# MCU.net
KiCad netlist of a schematic drawn in Altium Designer
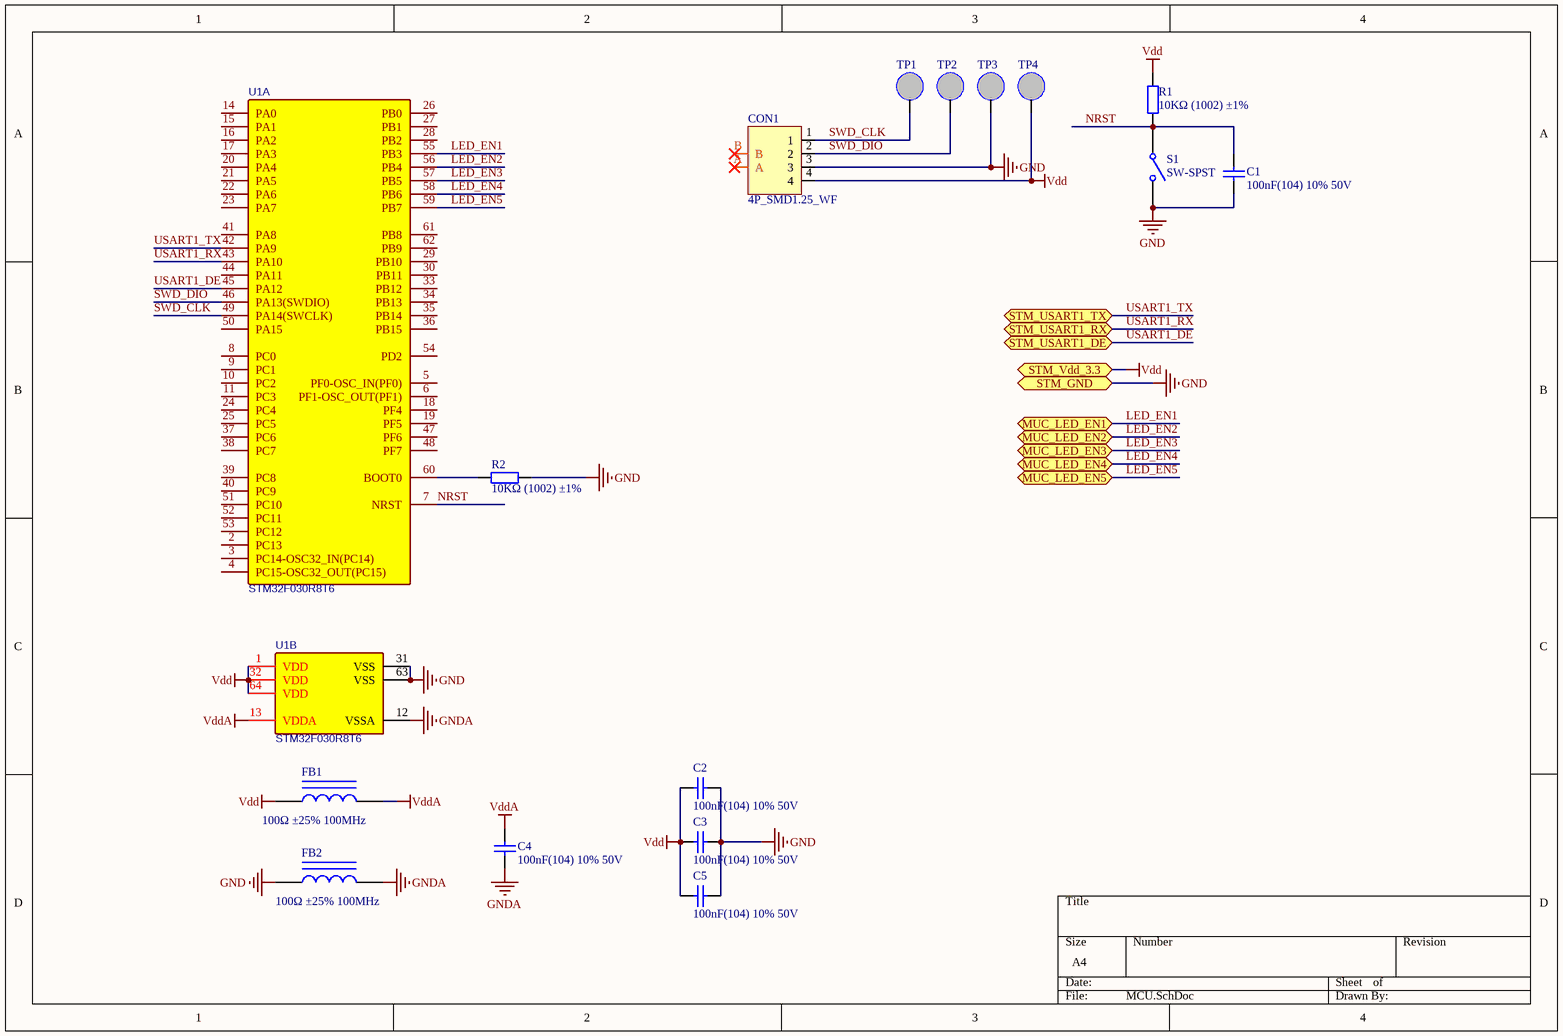
[diagram p0: MCU.SchDoc]

(export (version "E")
  (design (tool "Eeschema 10.0.6"))
  (components
    (comp (ref "C1")
      (value "100nF(104) 10% 50V")
      (footprint "0805_C")
      (description "贴片电容")
      (libsource (lib "Miscellaneous Devices LC") (part "0805 100nF(104) 10% 50V"))
    )
    (comp (ref "C2")
      (value "100nF(104) 10% 50V")
      (footprint "0805_C")
      (description "贴片电容")
      (libsource (lib "Miscellaneous Devices LC") (part "0805 100nF(104) 10% 50V"))
    )
    (comp (ref "C3")
      (value "100nF(104) 10% 50V")
      (footprint "0805_C")
      (description "贴片电容")
      (libsource (lib "Miscellaneous Devices LC") (part "0805 100nF(104) 10% 50V"))
    )
    (comp (ref "C4")
      (value "100nF(104) 10% 50V")
      (footprint "0805_C")
      (description "贴片电容")
      (libsource (lib "Miscellaneous Devices LC") (part "0805 100nF(104) 10% 50V"))
    )
    (comp (ref "C5")
      (value "100nF(104) 10% 50V")
      (footprint "0805_C")
      (description "贴片电容")
      (libsource (lib "Miscellaneous Devices LC") (part "0805 100nF(104) 10% 50V"))
    )
    (comp (ref "CON1")
      (value "4P_SMD1.25_WF")
      (footprint "MX 1.25-LS-4P")
      (libsource (lib "mylib") (part "4P_XH2.54_W"))
    )
    (comp (ref "FB1")
      (value "100Ω ±25% 100MHz")
      (footprint "0805_L")
      (description "贴片磁珠")
      (libsource (lib "Miscellaneous Devices LC") (part "0805 100Ω 25% 100MHz"))
    )
    (comp (ref "FB2")
      (value "100Ω ±25% 100MHz")
      (footprint "0805_L")
      (description "贴片磁珠")
      (libsource (lib "Miscellaneous Devices LC") (part "0805 100Ω 25% 100MHz"))
    )
    (comp (ref "R1")
      (value "10KΩ (1002) ±1%")
      (footprint "0805_R")
      (description "贴片电阻")
      (libsource (lib "Miscellaneous Devices LC") (part "0805 10KΩ (1002) 1%"))
    )
    (comp (ref "R2")
      (value "10KΩ (1002) ±1%")
      (footprint "0805_R")
      (description "贴片电阻")
      (libsource (lib "") (part "0805 10KΩ (1002) 1%_1"))
    )
    (comp (ref "S1")
      (value "SW-SPST")
      (footprint "key")
      (description "Single-Pole, Single-Throw Switch")
      (fields (field (name "PUBLISHER") "Altium Limited"))
      (libsource (lib "Miscellaneous Devices") (part "SW-SPST"))
    )
    (comp (ref "TP1") (value "TP") (footprint "TP") (libsource (lib "mylib") (part "TP")))
    (comp (ref "TP2") (value "TP") (footprint "TP") (libsource (lib "mylib") (part "TP")))
    (comp (ref "TP3") (value "TP") (footprint "TP") (libsource (lib "mylib") (part "TP")))
    (comp (ref "TP4") (value "TP") (footprint "TP") (libsource (lib "mylib") (part "TP")))
    (comp (ref "U1")
      (value "STM32F030R8T6")
      (footprint "LQFP-64_10X10X05P")
      (fields (field (name "BOM_SUPPLIER PART") "C39105") (field (name "SUBPART_NO") "1"))
      (libsource (lib "mylib") (part "STM32F030R8T6"))
    )
  )
  (nets
    (net (code "1") (name "/LED_EN1") (class "Default")
      (node (ref "U1") (pin "55") (pinfunction "PB3_55") (pintype "passive"))
    )
    (net (code "2") (name "/LED_EN2") (class "Default")
      (node (ref "U1") (pin "56") (pinfunction "PB4_56") (pintype "passive"))
    )
    (net (code "3") (name "/LED_EN3") (class "Default")
      (node (ref "U1") (pin "57") (pinfunction "PB5_57") (pintype "passive"))
    )
    (net (code "4") (name "/LED_EN4") (class "Default")
      (node (ref "U1") (pin "58") (pinfunction "PB6_58") (pintype "passive"))
    )
    (net (code "5") (name "/LED_EN5") (class "Default")
      (node (ref "U1") (pin "59") (pinfunction "PB7_59") (pintype "passive"))
    )
    (net (code "6") (name "/NRST") (class "Default")
      (node (ref "C1") (pin "2") (pinfunction "2_2") (pintype "passive"))
      (node (ref "R1") (pin "1") (pinfunction "1_1") (pintype "passive"))
      (node (ref "S1") (pin "1") (pinfunction "COMMON_1") (pintype "passive"))
      (node (ref "U1") (pin "7") (pinfunction "NRST_7") (pintype "passive"))
    )
    (net (code "7") (name "/SWD_CLK") (class "Default")
      (node (ref "CON1") (pin "1") (pinfunction "1_1") (pintype "passive"))
      (node (ref "TP1") (pin "1") (pinfunction "1_1") (pintype "passive"))
      (node (ref "U1") (pin "49") (pinfunction "PA14(SWCLK)_49") (pintype "passive"))
    )
    (net (code "8") (name "/SWD_DIO") (class "Default")
      (node (ref "CON1") (pin "2") (pinfunction "2_2") (pintype "passive"))
      (node (ref "TP2") (pin "1") (pinfunction "1_1") (pintype "passive"))
      (node (ref "U1") (pin "46") (pinfunction "PA13(SWDIO)_46") (pintype "passive"))
    )
    (net (code "9") (name "/USART1_DE") (class "Default")
      (node (ref "U1") (pin "45") (pinfunction "PA12_45") (pintype "passive"))
    )
    (net (code "10") (name "/USART1_RX") (class "Default")
      (node (ref "U1") (pin "43") (pinfunction "PA10_43") (pintype "passive"))
    )
    (net (code "11") (name "/USART1_TX") (class "Default")
      (node (ref "U1") (pin "42") (pinfunction "PA9_42") (pintype "passive"))
    )
    (net (code "12") (name "GND") (class "Default")
      (node (ref "C1") (pin "1") (pinfunction "1_1") (pintype "passive"))
      (node (ref "C2") (pin "1") (pinfunction "1_1") (pintype "passive"))
      (node (ref "C3") (pin "1") (pinfunction "1_1") (pintype "passive"))
      (node (ref "C5") (pin "1") (pinfunction "1_1") (pintype "passive"))
      (node (ref "CON1") (pin "3") (pinfunction "3_3") (pintype "passive"))
      (node (ref "FB2") (pin "1") (pinfunction "1_1") (pintype "passive"))
      (node (ref "R2") (pin "2") (pinfunction "2_2") (pintype "passive"))
      (node (ref "S1") (pin "2") (pinfunction "NO_2") (pintype "passive"))
      (node (ref "TP3") (pin "1") (pinfunction "1_1") (pintype "passive"))
      (node (ref "U1") (pin "31") (pinfunction "VSS_31") (pintype "passive"))
      (node (ref "U1") (pin "63") (pinfunction "VSS_63") (pintype "passive"))
    )
    (net (code "13") (name "GNDA") (class "Default")
      (node (ref "C4") (pin "1") (pinfunction "1_1") (pintype "passive"))
      (node (ref "FB2") (pin "2") (pinfunction "2_2") (pintype "passive"))
      (node (ref "U1") (pin "12") (pinfunction "VSSA_12") (pintype "passive"))
    )
    (net (code "14") (name "Net-(U1A-BOOT0)") (class "Default")
      (node (ref "R2") (pin "1") (pinfunction "1_1") (pintype "passive"))
      (node (ref "U1") (pin "60") (pinfunction "BOOT0_60") (pintype "passive"))
    )
    (net (code "15") (name "Vdd") (class "Default")
      (node (ref "C2") (pin "2") (pinfunction "2_2") (pintype "passive"))
      (node (ref "C3") (pin "2") (pinfunction "2_2") (pintype "passive"))
      (node (ref "C5") (pin "2") (pinfunction "2_2") (pintype "passive"))
      (node (ref "CON1") (pin "4") (pinfunction "4_4") (pintype "passive"))
      (node (ref "FB1") (pin "1") (pinfunction "1_1") (pintype "passive"))
      (node (ref "R1") (pin "2") (pinfunction "2_2") (pintype "passive"))
      (node (ref "TP4") (pin "1") (pinfunction "1_1") (pintype "passive"))
      (node (ref "U1") (pin "1") (pinfunction "VDD_1") (pintype "passive"))
      (node (ref "U1") (pin "32") (pinfunction "VDD_32") (pintype "passive"))
      (node (ref "U1") (pin "64") (pinfunction "VDD_64") (pintype "passive"))
    )
    (net (code "16") (name "VddA") (class "Default")
      (node (ref "C4") (pin "2") (pinfunction "2_2") (pintype "passive"))
      (node (ref "FB1") (pin "2") (pinfunction "2_2") (pintype "passive"))
      (node (ref "U1") (pin "13") (pinfunction "VDDA_13") (pintype "passive"))
    )
    (net (code "17") (name "unconnected-(CON1-PadA)") (class "Default")
      (node (ref "CON1") (pin "A") (pinfunction "A_A") (pintype "passive+no_connect"))
    )
    (net (code "18") (name "unconnected-(CON1-PadB)") (class "Default")
      (node (ref "CON1") (pin "B") (pinfunction "B_B") (pintype "passive+no_connect"))
    )
    (net (code "19") (name "unconnected-(U1A-PA0-Pad14)") (class "Default")
      (node (ref "U1") (pin "14") (pinfunction "PA0_14") (pintype "passive"))
    )
    (net (code "20") (name "unconnected-(U1A-PA1-Pad15)") (class "Default")
      (node (ref "U1") (pin "15") (pinfunction "PA1_15") (pintype "passive"))
    )
    (net (code "21") (name "unconnected-(U1A-PA2-Pad16)") (class "Default")
      (node (ref "U1") (pin "16") (pinfunction "PA2_16") (pintype "passive"))
    )
    (net (code "22") (name "unconnected-(U1A-PA3-Pad17)") (class "Default")
      (node (ref "U1") (pin "17") (pinfunction "PA3_17") (pintype "passive"))
    )
    (net (code "23") (name "unconnected-(U1A-PA4-Pad20)") (class "Default")
      (node (ref "U1") (pin "20") (pinfunction "PA4_20") (pintype "passive"))
    )
    (net (code "24") (name "unconnected-(U1A-PA5-Pad21)") (class "Default")
      (node (ref "U1") (pin "21") (pinfunction "PA5_21") (pintype "passive"))
    )
    (net (code "25") (name "unconnected-(U1A-PA6-Pad22)") (class "Default")
      (node (ref "U1") (pin "22") (pinfunction "PA6_22") (pintype "passive"))
    )
    (net (code "26") (name "unconnected-(U1A-PA7-Pad23)") (class "Default")
      (node (ref "U1") (pin "23") (pinfunction "PA7_23") (pintype "passive"))
    )
    (net (code "27") (name "unconnected-(U1A-PA8-Pad41)") (class "Default")
      (node (ref "U1") (pin "41") (pinfunction "PA8_41") (pintype "passive"))
    )
    (net (code "28") (name "unconnected-(U1A-PA11-Pad44)") (class "Default")
      (node (ref "U1") (pin "44") (pinfunction "PA11_44") (pintype "passive"))
    )
    (net (code "29") (name "unconnected-(U1A-PA15-Pad50)") (class "Default")
      (node (ref "U1") (pin "50") (pinfunction "PA15_50") (pintype "passive"))
    )
    (net (code "30") (name "unconnected-(U1A-PB0-Pad26)") (class "Default")
      (node (ref "U1") (pin "26") (pinfunction "PB0_26") (pintype "passive"))
    )
    (net (code "31") (name "unconnected-(U1A-PB1-Pad27)") (class "Default")
      (node (ref "U1") (pin "27") (pinfunction "PB1_27") (pintype "passive"))
    )
    (net (code "32") (name "unconnected-(U1A-PB2-Pad28)") (class "Default")
      (node (ref "U1") (pin "28") (pinfunction "PB2_28") (pintype "passive"))
    )
    (net (code "33") (name "unconnected-(U1A-PB8-Pad61)") (class "Default")
      (node (ref "U1") (pin "61") (pinfunction "PB8_61") (pintype "passive"))
    )
    (net (code "34") (name "unconnected-(U1A-PB9-Pad62)") (class "Default")
      (node (ref "U1") (pin "62") (pinfunction "PB9_62") (pintype "passive"))
    )
    (net (code "35") (name "unconnected-(U1A-PB10-Pad29)") (class "Default")
      (node (ref "U1") (pin "29") (pinfunction "PB10_29") (pintype "passive"))
    )
    (net (code "36") (name "unconnected-(U1A-PB11-Pad30)") (class "Default")
      (node (ref "U1") (pin "30") (pinfunction "PB11_30") (pintype "passive"))
    )
    (net (code "37") (name "unconnected-(U1A-PB12-Pad33)") (class "Default")
      (node (ref "U1") (pin "33") (pinfunction "PB12_33") (pintype "passive"))
    )
    (net (code "38") (name "unconnected-(U1A-PB13-Pad34)") (class "Default")
      (node (ref "U1") (pin "34") (pinfunction "PB13_34") (pintype "passive"))
    )
    (net (code "39") (name "unconnected-(U1A-PB14-Pad35)") (class "Default")
      (node (ref "U1") (pin "35") (pinfunction "PB14_35") (pintype "passive"))
    )
    (net (code "40") (name "unconnected-(U1A-PB15-Pad36)") (class "Default")
      (node (ref "U1") (pin "36") (pinfunction "PB15_36") (pintype "passive"))
    )
    (net (code "41") (name "unconnected-(U1A-PC0-Pad8)") (class "Default")
      (node (ref "U1") (pin "8") (pinfunction "PC0_8") (pintype "passive"))
    )
    (net (code "42") (name "unconnected-(U1A-PC1-Pad9)") (class "Default")
      (node (ref "U1") (pin "9") (pinfunction "PC1_9") (pintype "passive"))
    )
    (net (code "43") (name "unconnected-(U1A-PC2-Pad10)") (class "Default")
      (node (ref "U1") (pin "10") (pinfunction "PC2_10") (pintype "passive"))
    )
    (net (code "44") (name "unconnected-(U1A-PC3-Pad11)") (class "Default")
      (node (ref "U1") (pin "11") (pinfunction "PC3_11") (pintype "passive"))
    )
    (net (code "45") (name "unconnected-(U1A-PC4-Pad24)") (class "Default")
      (node (ref "U1") (pin "24") (pinfunction "PC4_24") (pintype "passive"))
    )
    (net (code "46") (name "unconnected-(U1A-PC5-Pad25)") (class "Default")
      (node (ref "U1") (pin "25") (pinfunction "PC5_25") (pintype "passive"))
    )
    (net (code "47") (name "unconnected-(U1A-PC6-Pad37)") (class "Default")
      (node (ref "U1") (pin "37") (pinfunction "PC6_37") (pintype "passive"))
    )
    (net (code "48") (name "unconnected-(U1A-PC7-Pad38)") (class "Default")
      (node (ref "U1") (pin "38") (pinfunction "PC7_38") (pintype "passive"))
    )
    (net (code "49") (name "unconnected-(U1A-PC8-Pad39)") (class "Default")
      (node (ref "U1") (pin "39") (pinfunction "PC8_39") (pintype "passive"))
    )
    (net (code "50") (name "unconnected-(U1A-PC9-Pad40)") (class "Default")
      (node (ref "U1") (pin "40") (pinfunction "PC9_40") (pintype "passive"))
    )
    (net (code "51") (name "unconnected-(U1A-PC10-Pad51)") (class "Default")
      (node (ref "U1") (pin "51") (pinfunction "PC10_51") (pintype "passive"))
    )
    (net (code "52") (name "unconnected-(U1A-PC11-Pad52)") (class "Default")
      (node (ref "U1") (pin "52") (pinfunction "PC11_52") (pintype "passive"))
    )
    (net (code "53") (name "unconnected-(U1A-PC12-Pad53)") (class "Default")
      (node (ref "U1") (pin "53") (pinfunction "PC12_53") (pintype "passive"))
    )
    (net (code "54") (name "unconnected-(U1A-PC13-Pad2)") (class "Default")
      (node (ref "U1") (pin "2") (pinfunction "PC13_2") (pintype "passive"))
    )
    (net (code "55") (name "unconnected-(U1A-PC14-OSC32_IN(PC14)-Pad3)") (class "Default")
      (node (ref "U1") (pin "3") (pinfunction "PC14-OSC32_IN(PC14)_3") (pintype "passive"))
    )
    (net (code "56") (name "unconnected-(U1A-PC15-OSC32_OUT(PC15)-Pad4)") (class "Default")
      (node (ref "U1") (pin "4") (pinfunction "PC15-OSC32_OUT(PC15)_4") (pintype "passive"))
    )
    (net (code "57") (name "unconnected-(U1A-PD2-Pad54)") (class "Default")
      (node (ref "U1") (pin "54") (pinfunction "PD2_54") (pintype "passive"))
    )
    (net (code "58") (name "unconnected-(U1A-PF0-OSC_IN(PF0)-Pad5)") (class "Default")
      (node (ref "U1") (pin "5") (pinfunction "PF0-OSC_IN(PF0)_5") (pintype "passive"))
    )
    (net (code "59") (name "unconnected-(U1A-PF1-OSC_OUT(PF1)-Pad6)") (class "Default")
      (node (ref "U1") (pin "6") (pinfunction "PF1-OSC_OUT(PF1)_6") (pintype "passive"))
    )
    (net (code "60") (name "unconnected-(U1A-PF4-Pad18)") (class "Default")
      (node (ref "U1") (pin "18") (pinfunction "PF4_18") (pintype "passive"))
    )
    (net (code "61") (name "unconnected-(U1A-PF5-Pad19)") (class "Default")
      (node (ref "U1") (pin "19") (pinfunction "PF5_19") (pintype "passive"))
    )
    (net (code "62") (name "unconnected-(U1A-PF6-Pad47)") (class "Default")
      (node (ref "U1") (pin "47") (pinfunction "PF6_47") (pintype "passive"))
    )
    (net (code "63") (name "unconnected-(U1A-PF7-Pad48)") (class "Default")
      (node (ref "U1") (pin "48") (pinfunction "PF7_48") (pintype "passive"))
    )
  )
)
